# K4S561632.net
KiCad netlist of a schematic drawn in Altium Designer
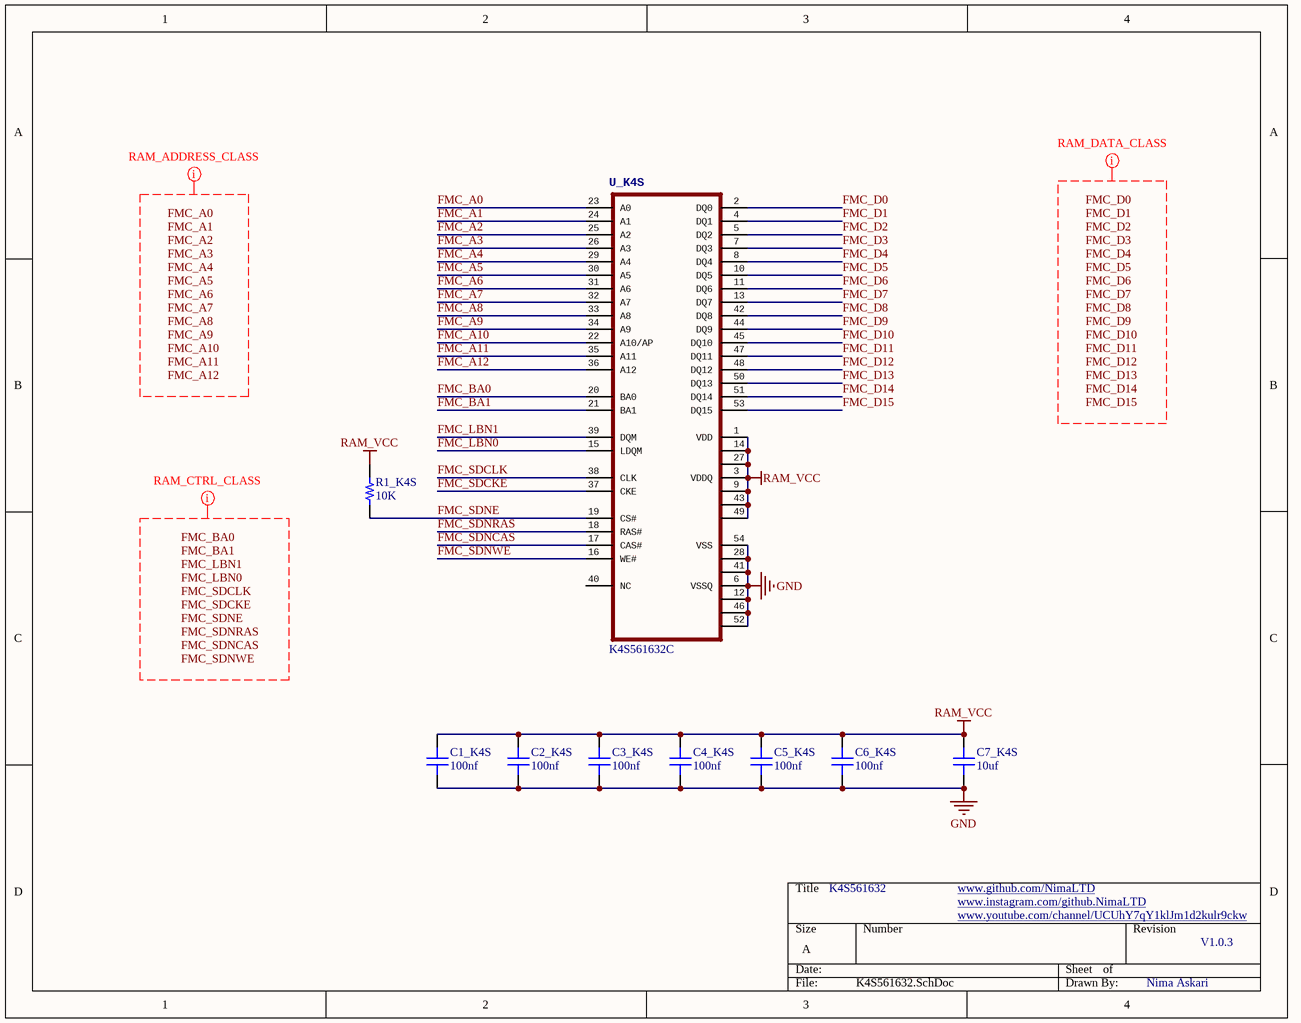
[diagram p0: K4S561632.SchDoc]

(export (version "E")
  (design (tool "Eeschema 10.0.6"))
  (components
    (comp (ref "C1_K4S")
      (value "100nf")
      (footprint "CAP 0805")
      (description "SMT Capacitor")
      (libsource (lib "CAPACITOR") (part "Cap SMD 0805"))
    )
    (comp (ref "C2_K4S")
      (value "100nf")
      (footprint "CAP 0805")
      (description "SMT Capacitor")
      (libsource (lib "CAPACITOR") (part "Cap SMD 0805"))
    )
    (comp (ref "C3_K4S")
      (value "100nf")
      (footprint "CAP 0805")
      (description "SMT Capacitor")
      (libsource (lib "CAPACITOR") (part "Cap SMD 0805"))
    )
    (comp (ref "C4_K4S")
      (value "100nf")
      (footprint "CAP 0805")
      (description "SMT Capacitor")
      (libsource (lib "CAPACITOR") (part "Cap SMD 0805"))
    )
    (comp (ref "C5_K4S")
      (value "100nf")
      (footprint "CAP 0805")
      (description "SMT Capacitor")
      (libsource (lib "CAPACITOR") (part "Cap SMD 0805"))
    )
    (comp (ref "C6_K4S")
      (value "100nf")
      (footprint "CAP 0805")
      (description "SMT Capacitor")
      (libsource (lib "CAPACITOR") (part "Cap SMD 0805"))
    )
    (comp (ref "C7_K4S")
      (value "10uf")
      (footprint "CAP 0805")
      (description "SMT Capacitor")
      (libsource (lib "CAPACITOR") (part "Cap SMD 0805"))
    )
    (comp (ref "R1_K4S")
      (value "10K")
      (footprint "RES 0805")
      (description "SMD Resistor")
      (libsource (lib "RESISTOR") (part "Res SMD 0805"))
    )
    (comp (ref "U_K4S")
      (value "SDRAM   4M x 16bit x 4 banks synchronous DRAM. 256 Mbit SDRAM.")
      (footprint "TSOP54_P0.8")
      (fields (field (name "MP") "K4S561632C"))
      (libsource (lib "IC") (part "K4S561632E-TC"))
    )
  )
  (nets
    (net (code "1") (name "/FMC_A0") (class "Default")
      (node (ref "U_K4S") (pin "23") (pinfunction "A0_23") (pintype "passive"))
    )
    (net (code "2") (name "/FMC_A1") (class "Default")
      (node (ref "U_K4S") (pin "24") (pinfunction "A1_24") (pintype "passive"))
    )
    (net (code "3") (name "/FMC_A2") (class "Default")
      (node (ref "U_K4S") (pin "25") (pinfunction "A2_25") (pintype "passive"))
    )
    (net (code "4") (name "/FMC_A3") (class "Default")
      (node (ref "U_K4S") (pin "26") (pinfunction "A3_26") (pintype "passive"))
    )
    (net (code "5") (name "/FMC_A4") (class "Default")
      (node (ref "U_K4S") (pin "29") (pinfunction "A4_29") (pintype "passive"))
    )
    (net (code "6") (name "/FMC_A5") (class "Default")
      (node (ref "U_K4S") (pin "30") (pinfunction "A5_30") (pintype "passive"))
    )
    (net (code "7") (name "/FMC_A6") (class "Default")
      (node (ref "U_K4S") (pin "31") (pinfunction "A6_31") (pintype "passive"))
    )
    (net (code "8") (name "/FMC_A7") (class "Default")
      (node (ref "U_K4S") (pin "32") (pinfunction "A7_32") (pintype "passive"))
    )
    (net (code "9") (name "/FMC_A8") (class "Default")
      (node (ref "U_K4S") (pin "33") (pinfunction "A8_33") (pintype "passive"))
    )
    (net (code "10") (name "/FMC_A9") (class "Default")
      (node (ref "U_K4S") (pin "34") (pinfunction "A9_34") (pintype "passive"))
    )
    (net (code "11") (name "/FMC_A10") (class "Default")
      (node (ref "U_K4S") (pin "22") (pinfunction "A10/AP_22") (pintype "passive"))
    )
    (net (code "12") (name "/FMC_A11") (class "Default")
      (node (ref "U_K4S") (pin "35") (pinfunction "A11_35") (pintype "passive"))
    )
    (net (code "13") (name "/FMC_A12") (class "Default")
      (node (ref "U_K4S") (pin "36") (pinfunction "A12_36") (pintype "passive"))
    )
    (net (code "14") (name "/FMC_BA0") (class "Default")
      (node (ref "U_K4S") (pin "20") (pinfunction "BA0_20") (pintype "passive"))
    )
    (net (code "15") (name "/FMC_BA1") (class "Default")
      (node (ref "U_K4S") (pin "21") (pinfunction "BA1_21") (pintype "passive"))
    )
    (net (code "16") (name "/FMC_D0") (class "Default")
      (node (ref "U_K4S") (pin "2") (pinfunction "DQ0_2") (pintype "passive"))
    )
    (net (code "17") (name "/FMC_D1") (class "Default")
      (node (ref "U_K4S") (pin "4") (pinfunction "DQ1_4") (pintype "passive"))
    )
    (net (code "18") (name "/FMC_D2") (class "Default")
      (node (ref "U_K4S") (pin "5") (pinfunction "DQ2_5") (pintype "passive"))
    )
    (net (code "19") (name "/FMC_D3") (class "Default")
      (node (ref "U_K4S") (pin "7") (pinfunction "DQ3_7") (pintype "passive"))
    )
    (net (code "20") (name "/FMC_D4") (class "Default")
      (node (ref "U_K4S") (pin "8") (pinfunction "DQ4_8") (pintype "passive"))
    )
    (net (code "21") (name "/FMC_D5") (class "Default")
      (node (ref "U_K4S") (pin "10") (pinfunction "DQ5_10") (pintype "passive"))
    )
    (net (code "22") (name "/FMC_D6") (class "Default")
      (node (ref "U_K4S") (pin "11") (pinfunction "DQ6_11") (pintype "passive"))
    )
    (net (code "23") (name "/FMC_D7") (class "Default")
      (node (ref "U_K4S") (pin "13") (pinfunction "DQ7_13") (pintype "passive"))
    )
    (net (code "24") (name "/FMC_D8") (class "Default")
      (node (ref "U_K4S") (pin "42") (pinfunction "DQ8_42") (pintype "passive"))
    )
    (net (code "25") (name "/FMC_D9") (class "Default")
      (node (ref "U_K4S") (pin "44") (pinfunction "DQ9_44") (pintype "passive"))
    )
    (net (code "26") (name "/FMC_D10") (class "Default")
      (node (ref "U_K4S") (pin "45") (pinfunction "DQ10_45") (pintype "passive"))
    )
    (net (code "27") (name "/FMC_D11") (class "Default")
      (node (ref "U_K4S") (pin "47") (pinfunction "DQ11_47") (pintype "passive"))
    )
    (net (code "28") (name "/FMC_D12") (class "Default")
      (node (ref "U_K4S") (pin "48") (pinfunction "DQ12_48") (pintype "passive"))
    )
    (net (code "29") (name "/FMC_D13") (class "Default")
      (node (ref "U_K4S") (pin "50") (pinfunction "DQ13_50") (pintype "passive"))
    )
    (net (code "30") (name "/FMC_D14") (class "Default")
      (node (ref "U_K4S") (pin "51") (pinfunction "DQ14_51") (pintype "passive"))
    )
    (net (code "31") (name "/FMC_D15") (class "Default")
      (node (ref "U_K4S") (pin "53") (pinfunction "DQ15_53") (pintype "passive"))
    )
    (net (code "32") (name "/FMC_LBN0") (class "Default")
      (node (ref "U_K4S") (pin "15") (pinfunction "LDQM_15") (pintype "passive"))
    )
    (net (code "33") (name "/FMC_LBN1") (class "Default")
      (node (ref "U_K4S") (pin "39") (pinfunction "DQM_39") (pintype "passive"))
    )
    (net (code "34") (name "/FMC_SDCKE") (class "Default")
      (node (ref "U_K4S") (pin "37") (pinfunction "CKE_37") (pintype "passive"))
    )
    (net (code "35") (name "/FMC_SDCLK") (class "Default")
      (node (ref "U_K4S") (pin "38") (pinfunction "CLK_38") (pintype "passive"))
    )
    (net (code "36") (name "/FMC_SDNCAS") (class "Default")
      (node (ref "U_K4S") (pin "17") (pinfunction "CAS#_17") (pintype "passive"))
    )
    (net (code "37") (name "/FMC_SDNE") (class "Default")
      (node (ref "R1_K4S") (pin "1") (pinfunction "1_1") (pintype "passive"))
      (node (ref "U_K4S") (pin "19") (pinfunction "CS#_19") (pintype "passive"))
    )
    (net (code "38") (name "/FMC_SDNRAS") (class "Default")
      (node (ref "U_K4S") (pin "18") (pinfunction "RAS#_18") (pintype "passive"))
    )
    (net (code "39") (name "/FMC_SDNWE") (class "Default")
      (node (ref "U_K4S") (pin "16") (pinfunction "WE#_16") (pintype "passive"))
    )
    (net (code "40") (name "GND") (class "Default")
      (node (ref "C1_K4S") (pin "1") (pinfunction "1_1") (pintype "passive"))
      (node (ref "C2_K4S") (pin "1") (pinfunction "1_1") (pintype "passive"))
      (node (ref "C3_K4S") (pin "1") (pinfunction "1_1") (pintype "passive"))
      (node (ref "C4_K4S") (pin "1") (pinfunction "1_1") (pintype "passive"))
      (node (ref "C5_K4S") (pin "1") (pinfunction "1_1") (pintype "passive"))
      (node (ref "C6_K4S") (pin "1") (pinfunction "1_1") (pintype "passive"))
      (node (ref "C7_K4S") (pin "1") (pinfunction "1_1") (pintype "passive"))
      (node (ref "U_K4S") (pin "12") (pinfunction "VSSQ@12_12") (pintype "power_in"))
      (node (ref "U_K4S") (pin "28") (pinfunction "VSS@28_28") (pintype "power_in"))
      (node (ref "U_K4S") (pin "41") (pinfunction "VSS@41_41") (pintype "power_in"))
      (node (ref "U_K4S") (pin "46") (pinfunction "VSSQ@46_46") (pintype "power_in"))
      (node (ref "U_K4S") (pin "52") (pinfunction "VSSQ@52_52") (pintype "power_in"))
      (node (ref "U_K4S") (pin "54") (pinfunction "VSS_54") (pintype "power_in"))
      (node (ref "U_K4S") (pin "6") (pinfunction "VSSQ_6") (pintype "power_in"))
    )
    (net (code "41") (name "RAM_VCC") (class "Default")
      (node (ref "C1_K4S") (pin "2") (pinfunction "2_2") (pintype "passive"))
      (node (ref "C2_K4S") (pin "2") (pinfunction "2_2") (pintype "passive"))
      (node (ref "C3_K4S") (pin "2") (pinfunction "2_2") (pintype "passive"))
      (node (ref "C4_K4S") (pin "2") (pinfunction "2_2") (pintype "passive"))
      (node (ref "C5_K4S") (pin "2") (pinfunction "2_2") (pintype "passive"))
      (node (ref "C6_K4S") (pin "2") (pinfunction "2_2") (pintype "passive"))
      (node (ref "C7_K4S") (pin "2") (pinfunction "2_2") (pintype "passive"))
      (node (ref "R1_K4S") (pin "2") (pinfunction "2_2") (pintype "passive"))
      (node (ref "U_K4S") (pin "1") (pinfunction "VDD_1") (pintype "power_in"))
      (node (ref "U_K4S") (pin "14") (pinfunction "VDD@14_14") (pintype "power_in"))
      (node (ref "U_K4S") (pin "27") (pinfunction "VDD@27_27") (pintype "power_in"))
      (node (ref "U_K4S") (pin "3") (pinfunction "VDDQ_3") (pintype "power_in"))
      (node (ref "U_K4S") (pin "43") (pinfunction "VDDQ@43_43") (pintype "power_in"))
      (node (ref "U_K4S") (pin "49") (pinfunction "VDDQ@49_49") (pintype "power_in"))
      (node (ref "U_K4S") (pin "9") (pinfunction "VDDQ@9_9") (pintype "power_in"))
    )
    (net (code "42") (name "unconnected-(U_K4S-NC-Pad40)") (class "Default")
      (node (ref "U_K4S") (pin "40") (pinfunction "NC_40") (pintype "passive"))
    )
  )
)
